# em_probe_input_filter.net
KiCad netlist of a schematic drawn in EAGLE
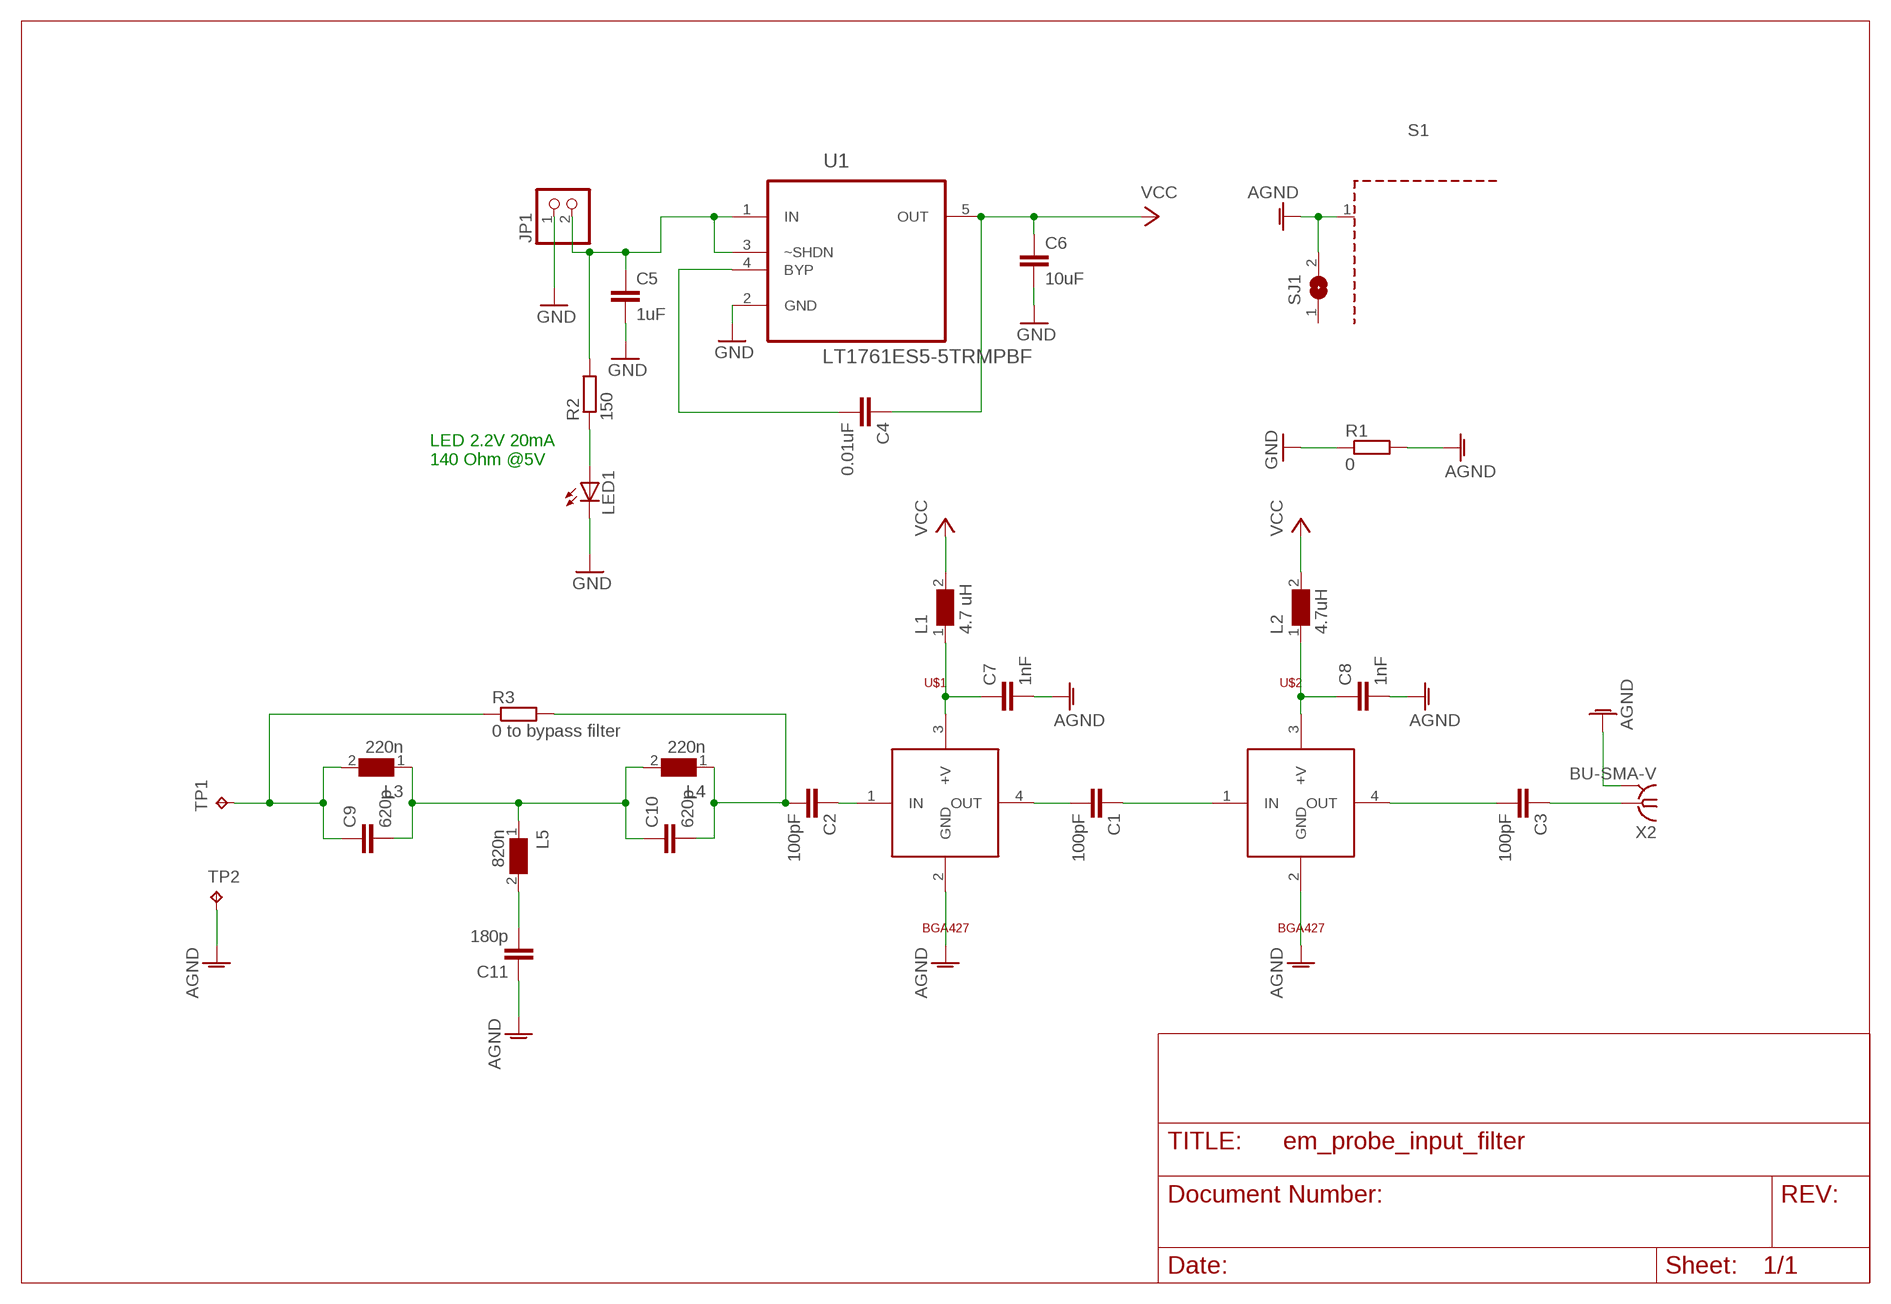
[diagram p0: schematic, sheet 1]

(export (version "E")
  (design (tool "Eeschema 10.0.6"))
  (components
    (comp (ref "C1")
      (value "100pF")
      (footprint "eagle-import:C0805")
      (libsource (lib "eagle-import") (part "C-EUC0805"))
    )
    (comp (ref "C2")
      (value "100pF")
      (footprint "eagle-import:C0805")
      (libsource (lib "eagle-import") (part "C-EUC0805"))
    )
    (comp (ref "C3")
      (value "100pF")
      (footprint "eagle-import:C0805")
      (libsource (lib "eagle-import") (part "C-EUC0805"))
    )
    (comp (ref "C4")
      (value "0.01uF")
      (footprint "eagle-import:C0805")
      (libsource (lib "eagle-import") (part "C-EUC0805"))
    )
    (comp (ref "C5")
      (value "1uF")
      (footprint "eagle-import:C0805")
      (libsource (lib "eagle-import") (part "C-EUC0805"))
    )
    (comp (ref "C6")
      (value "10uF")
      (footprint "eagle-import:C0805")
      (libsource (lib "eagle-import") (part "C-EUC0805"))
    )
    (comp (ref "C7")
      (value "1nF")
      (footprint "eagle-import:C0805")
      (libsource (lib "eagle-import") (part "C-EUC0805"))
    )
    (comp (ref "C8")
      (value "1nF")
      (footprint "eagle-import:C0805")
      (libsource (lib "eagle-import") (part "C-EUC0805"))
    )
    (comp (ref "C9")
      (value "620p")
      (footprint "eagle-import:C0805")
      (libsource (lib "eagle-import") (part "C-EUC0805"))
    )
    (comp (ref "C10")
      (value "620p")
      (footprint "eagle-import:C0805")
      (libsource (lib "eagle-import") (part "C-EUC0805"))
    )
    (comp (ref "C11")
      (value "180p")
      (footprint "eagle-import:C0805")
      (libsource (lib "eagle-import") (part "C-EUC0805"))
    )
    (comp (ref "JP1")
      (value "PINHD-1X2/90")
      (footprint "eagle-import:1X02_90")
      (libsource (lib "eagle-import") (part "PINHD-1X2/90"))
    )
    (comp (ref "L1")
      (value "4.7 uH")
      (footprint "eagle-import:WE-RFH")
      (fields (field (name "MPN") "744758347A"))
      (libsource (lib "eagle-import") (part "WE-RFH-744758347A"))
    )
    (comp (ref "L2")
      (value "4.7uH")
      (footprint "eagle-import:WE-RFH")
      (fields (field (name "MPN") "744758347A"))
      (libsource (lib "eagle-import") (part "WE-RFH-744758347A"))
    )
    (comp (ref "L3")
      (value "220n")
      (footprint "eagle-import:WE-RFH")
      (fields (field (name "MPN") "744758347A"))
      (libsource (lib "eagle-import") (part "WE-RFH-744758347A"))
    )
    (comp (ref "L4")
      (value "220n")
      (footprint "eagle-import:WE-RFH")
      (fields (field (name "MPN") "744758347A"))
      (libsource (lib "eagle-import") (part "WE-RFH-744758347A"))
    )
    (comp (ref "L5")
      (value "820n")
      (footprint "eagle-import:WE-RFH")
      (fields (field (name "MPN") "744758347A"))
      (libsource (lib "eagle-import") (part "WE-RFH-744758347A"))
    )
    (comp (ref "LED1")
      (value "LEDCHIPLED_0805")
      (footprint "eagle-import:CHIPLED_0805")
      (libsource (lib "eagle-import") (part "LEDCHIPLED_0805"))
    )
    (comp (ref "R1")
      (value "0")
      (footprint "eagle-import:R0805")
      (libsource (lib "eagle-import") (part "R-EU_R0805"))
    )
    (comp (ref "R2")
      (value "150")
      (footprint "eagle-import:R0805")
      (libsource (lib "eagle-import") (part "R-EU_R0805"))
    )
    (comp (ref "R3")
      (value "0 to bypass filter")
      (footprint "eagle-import:R0805")
      (libsource (lib "eagle-import") (part "R-EU_R0805"))
    )
    (comp (ref "S1")
      (value "WE-SHC_36103305")
      (footprint "eagle-import:WE-SHC_36103305")
      (fields (field (name "MPN") "36103305"))
      (libsource (lib "eagle-import") (part "WE-SHC_36103305"))
    )
    (comp (ref "SJ1") (value "SJ") (footprint "eagle-import:SJ") (libsource (lib "eagle-import") (part "SJ")))
    (comp (ref "TP1")
      (value "TPTP15R")
      (footprint "eagle-import:TP15R")
      (libsource (lib "eagle-import") (part "TPTP15R"))
    )
    (comp (ref "TP2")
      (value "TPTP15R")
      (footprint "eagle-import:TP15R")
      (libsource (lib "eagle-import") (part "TPTP15R"))
    )
    (comp (ref "U$1")
      (value "BGA427")
      (footprint "eagle-import:SOT343")
      (libsource (lib "eagle-import") (part "BGA427"))
    )
    (comp (ref "U$2")
      (value "BGA427")
      (footprint "eagle-import:SOT343")
      (libsource (lib "eagle-import") (part "BGA427"))
    )
    (comp (ref "U1")
      (value "LT1761ES5-5TRMPBF")
      (footprint "eagle-import:SOT95P280X100-5N")
      (fields (field (name "MPN") "LT1761ES5-5#TRMPBF"))
      (libsource (lib "eagle-import") (part "LT1761ES5-5TRMPBF"))
    )
    (comp (ref "X2")
      (value "BU-SMA-V")
      (footprint "eagle-import:BU-SMA-V")
      (libsource (lib "eagle-import") (part "BU-SMA-V"))
    )
  )
  (nets
    (net (code "1") (name "AGND") (class "Default")
      (node (ref "C11") (pin "1") (pinfunction "1_1") (pintype "passive"))
      (node (ref "C7") (pin "2") (pinfunction "2_2") (pintype "passive"))
      (node (ref "C8") (pin "2") (pinfunction "2_2") (pintype "passive"))
      (node (ref "R1") (pin "2") (pinfunction "2_2") (pintype "passive"))
      (node (ref "S1") (pin "1") (pinfunction "GND_1") (pintype "power_in"))
      (node (ref "SJ1") (pin "2") (pinfunction "2_2") (pintype "passive"))
      (node (ref "TP2") (pin "TP") (pinfunction "TP_TP") (pintype "input"))
      (node (ref "U$1") (pin "2") (pinfunction "GND_2") (pintype "bidirectional"))
      (node (ref "U$2") (pin "2") (pinfunction "GND_2") (pintype "bidirectional"))
      (node (ref "X2") (pin "2") (pinfunction "2_2") (pintype "passive"))
      (node (ref "X2") (pin "3") (pinfunction "2_3") (pintype "passive"))
      (node (ref "X2") (pin "4") (pinfunction "2_4") (pintype "passive"))
      (node (ref "X2") (pin "5") (pinfunction "2_5") (pintype "passive"))
    )
    (net (code "2") (name "GND") (class "Default")
      (node (ref "C5") (pin "2") (pinfunction "2_2") (pintype "passive"))
      (node (ref "C6") (pin "2") (pinfunction "2_2") (pintype "passive"))
      (node (ref "JP1") (pin "1") (pinfunction "1_1") (pintype "passive"))
      (node (ref "LED1") (pin "C") (pinfunction "C_C") (pintype "passive"))
      (node (ref "R1") (pin "1") (pinfunction "1_1") (pintype "passive"))
      (node (ref "U1") (pin "2") (pinfunction "GND_2") (pintype "passive"))
    )
    (net (code "3") (name "Net-(C3-Pad1)") (class "Default")
      (node (ref "C3") (pin "1") (pinfunction "1_1") (pintype "passive"))
      (node (ref "X2") (pin "1") (pinfunction "1_1") (pintype "passive"))
    )
    (net (code "4") (name "Net-(C9-Pad1)") (class "Default")
      (node (ref "C9") (pin "1") (pinfunction "1_1") (pintype "passive"))
      (node (ref "L3") (pin "2") (pinfunction "2_2") (pintype "passive"))
      (node (ref "R3") (pin "1") (pinfunction "1_1") (pintype "passive"))
      (node (ref "TP1") (pin "TP") (pinfunction "TP_TP") (pintype "input"))
    )
    (net (code "5") (name "Net-(C10-Pad1)") (class "Default")
      (node (ref "C10") (pin "1") (pinfunction "1_1") (pintype "passive"))
      (node (ref "C9") (pin "2") (pinfunction "2_2") (pintype "passive"))
      (node (ref "L3") (pin "1") (pinfunction "1_1") (pintype "passive"))
      (node (ref "L4") (pin "2") (pinfunction "2_2") (pintype "passive"))
      (node (ref "L5") (pin "1") (pinfunction "1_1") (pintype "passive"))
    )
    (net (code "6") (name "Net-(C10-Pad2)") (class "Default")
      (node (ref "C10") (pin "2") (pinfunction "2_2") (pintype "passive"))
      (node (ref "C2") (pin "2") (pinfunction "2_2") (pintype "passive"))
      (node (ref "L4") (pin "1") (pinfunction "1_1") (pintype "passive"))
      (node (ref "R3") (pin "2") (pinfunction "2_2") (pintype "passive"))
    )
    (net (code "7") (name "Net-(C11-Pad2)") (class "Default")
      (node (ref "C11") (pin "2") (pinfunction "2_2") (pintype "passive"))
      (node (ref "L5") (pin "2") (pinfunction "2_2") (pintype "passive"))
    )
    (net (code "8") (name "Net-(LED1-PadA)") (class "Default")
      (node (ref "LED1") (pin "A") (pinfunction "A_A") (pintype "passive"))
      (node (ref "R2") (pin "1") (pinfunction "1_1") (pintype "passive"))
    )
    (net (code "9") (name "Net-(U$1-+V)") (class "Default")
      (node (ref "C7") (pin "1") (pinfunction "1_1") (pintype "passive"))
      (node (ref "L1") (pin "1") (pinfunction "1_1") (pintype "passive"))
      (node (ref "U$1") (pin "3") (pinfunction "+V_3") (pintype "bidirectional"))
    )
    (net (code "10") (name "Net-(U$1-IN)") (class "Default")
      (node (ref "C2") (pin "1") (pinfunction "1_1") (pintype "passive"))
      (node (ref "U$1") (pin "1") (pinfunction "IN_1") (pintype "bidirectional"))
    )
    (net (code "11") (name "Net-(U$1-OUT)") (class "Default")
      (node (ref "C1") (pin "2") (pinfunction "2_2") (pintype "passive"))
      (node (ref "U$1") (pin "4") (pinfunction "OUT_4") (pintype "bidirectional"))
    )
    (net (code "12") (name "Net-(U$2-+V)") (class "Default")
      (node (ref "C8") (pin "1") (pinfunction "1_1") (pintype "passive"))
      (node (ref "L2") (pin "1") (pinfunction "1_1") (pintype "passive"))
      (node (ref "U$2") (pin "3") (pinfunction "+V_3") (pintype "bidirectional"))
    )
    (net (code "13") (name "Net-(U$2-IN)") (class "Default")
      (node (ref "C1") (pin "1") (pinfunction "1_1") (pintype "passive"))
      (node (ref "U$2") (pin "1") (pinfunction "IN_1") (pintype "bidirectional"))
    )
    (net (code "14") (name "Net-(U$2-OUT)") (class "Default")
      (node (ref "C3") (pin "2") (pinfunction "2_2") (pintype "passive"))
      (node (ref "U$2") (pin "4") (pinfunction "OUT_4") (pintype "bidirectional"))
    )
    (net (code "15") (name "Net-(U1-BYP)") (class "Default")
      (node (ref "C4") (pin "2") (pinfunction "2_2") (pintype "passive"))
      (node (ref "U1") (pin "4") (pinfunction "BYP_4") (pintype "input"))
    )
    (net (code "16") (name "Net-(U1-IN)") (class "Default")
      (node (ref "C5") (pin "1") (pinfunction "1_1") (pintype "passive"))
      (node (ref "JP1") (pin "2") (pinfunction "2_2") (pintype "passive"))
      (node (ref "R2") (pin "2") (pinfunction "2_2") (pintype "passive"))
      (node (ref "U1") (pin "1") (pinfunction "IN_1") (pintype "input"))
      (node (ref "U1") (pin "3") (pinfunction "~{SHDN}_3") (pintype "input"))
    )
    (net (code "17") (name "VCC") (class "Default")
      (node (ref "C4") (pin "1") (pinfunction "1_1") (pintype "passive"))
      (node (ref "C6") (pin "1") (pinfunction "1_1") (pintype "passive"))
      (node (ref "L1") (pin "2") (pinfunction "2_2") (pintype "passive"))
      (node (ref "L2") (pin "2") (pinfunction "2_2") (pintype "passive"))
      (node (ref "U1") (pin "5") (pinfunction "OUT_5") (pintype "output"))
    )
    (net (code "18") (name "unconnected-(SJ1-Pad1)") (class "Default")
      (node (ref "SJ1") (pin "1") (pinfunction "1_1") (pintype "passive"))
    )
  )
)
